# ESC.net
KiCad netlist of a schematic drawn in Altium Designer
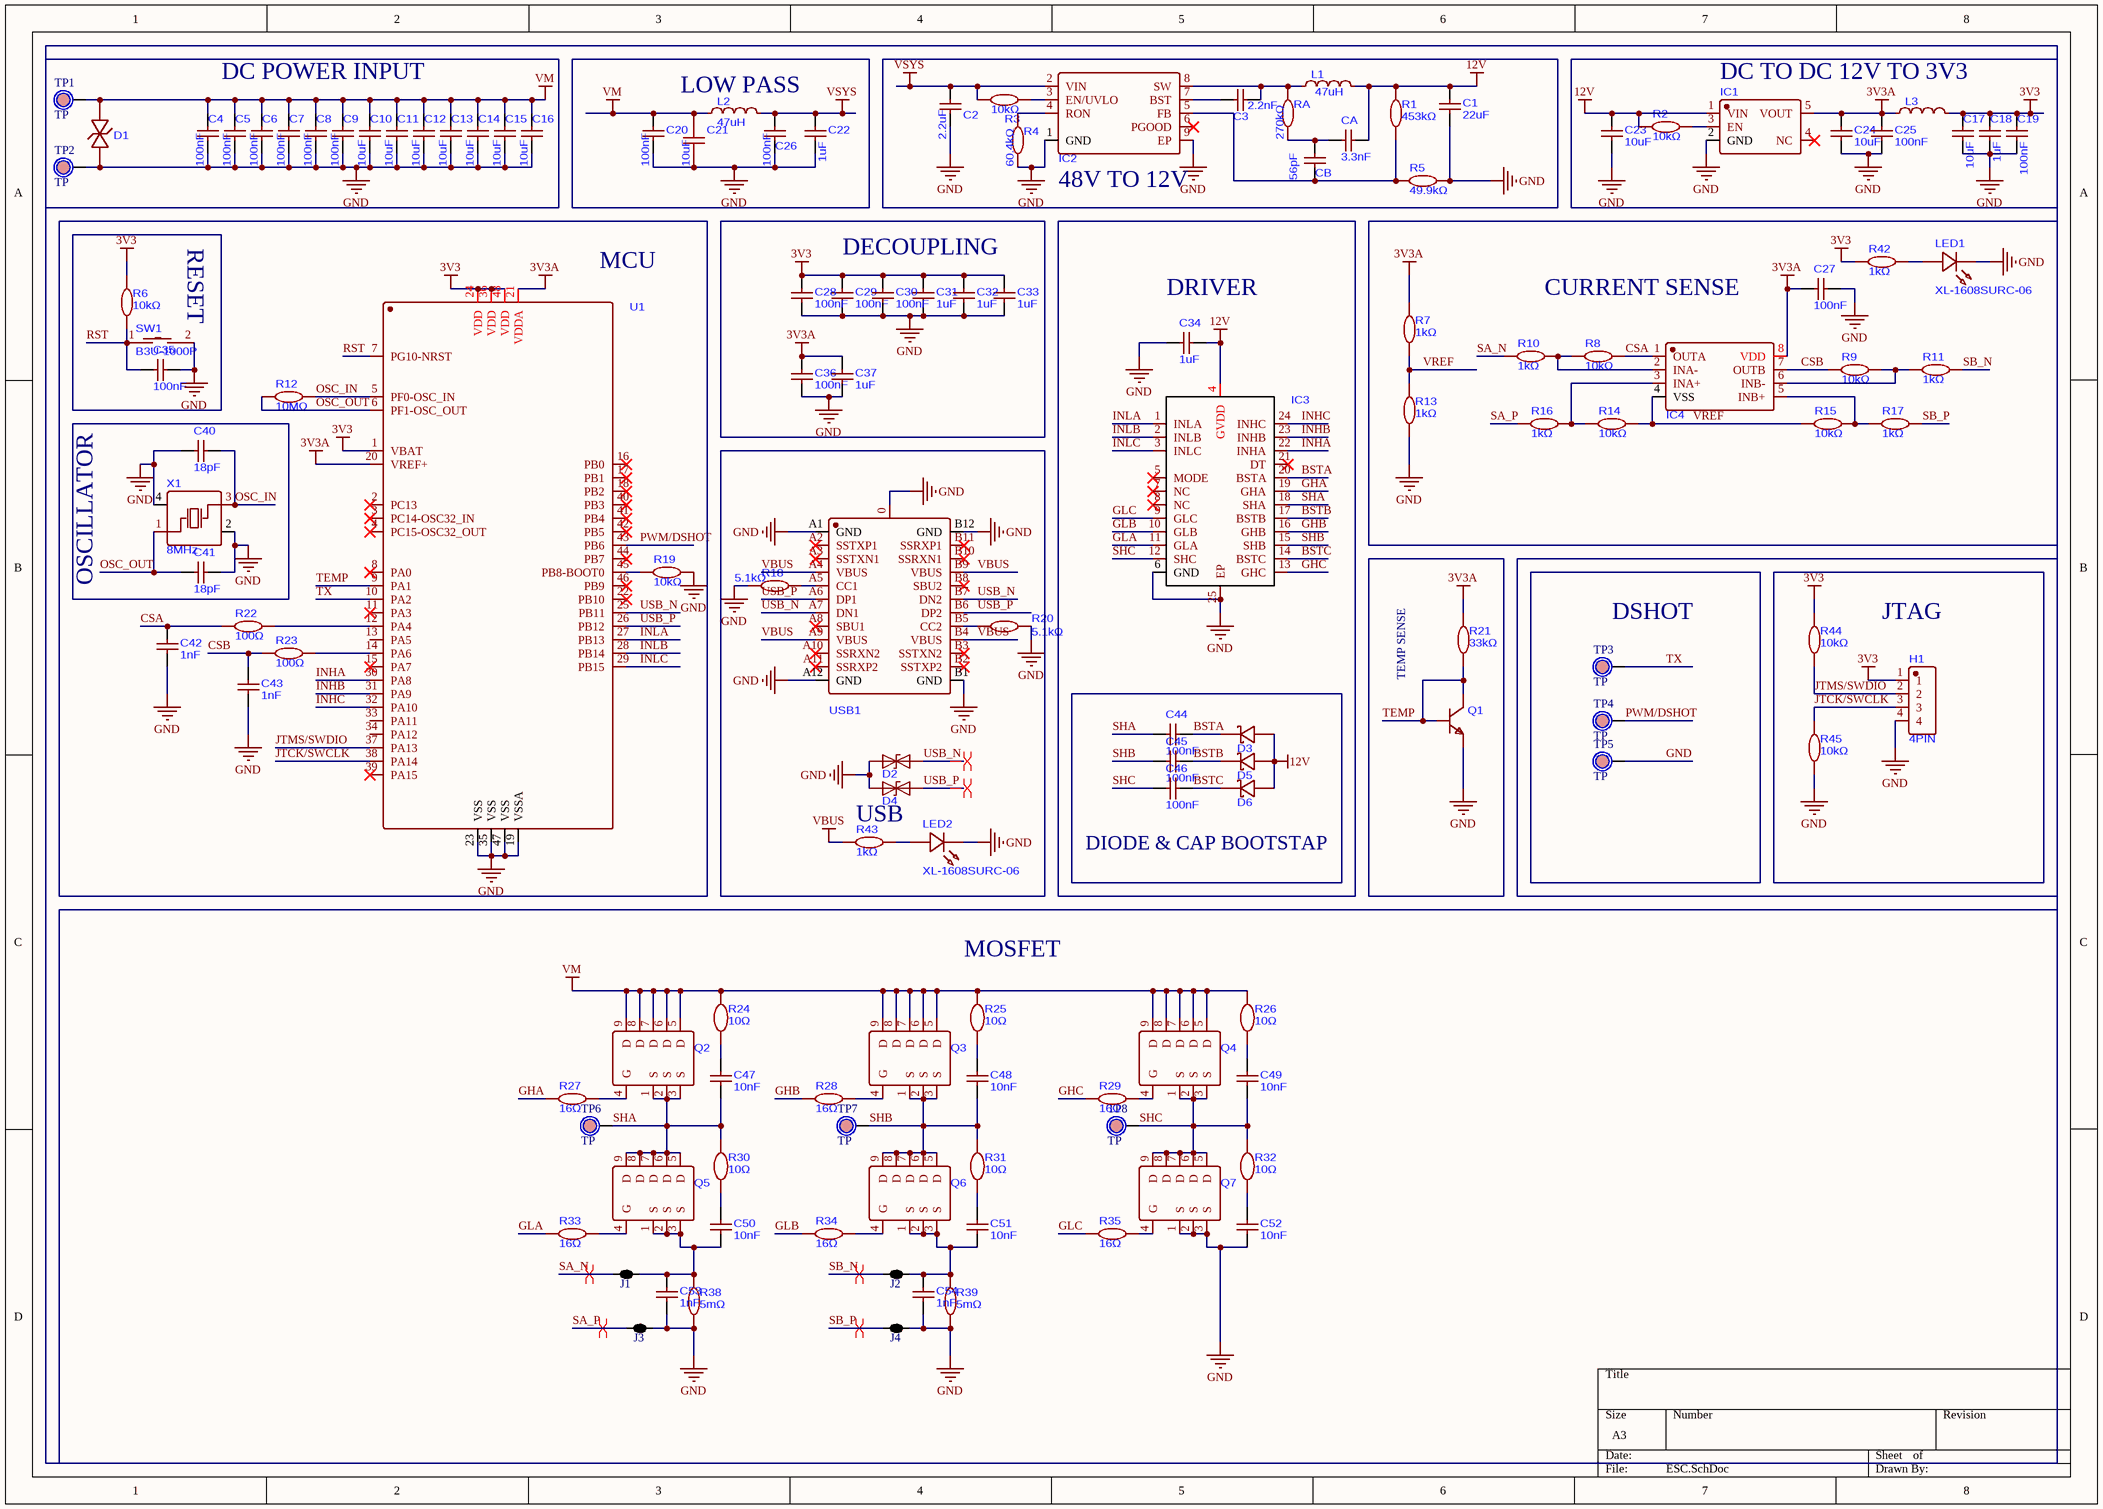
[diagram p0: ESC.SchDoc]

(export (version "E")
  (design (tool "Eeschema 10.0.6"))
  (components
    (comp (ref "C1")
      (value "22uF")
      (footprint "C0603")
      (description "CAP CER 22uF 25V 0603")
      (libsource (lib "ESC") (part "GRM188C61E226ME01D"))
    )
    (comp (ref "C2")
      (value "2.2uF")
      (footprint "C0805")
      (description "CAP CER 2.2uF 100V X7R 0805")
      (libsource (lib "ESC") (part "HHV0805R7225K101NSLJ"))
    )
    (comp (ref "C3")
      (value "2.2nF")
      (footprint "C0402")
      (description "CAP CER 2.2nF 50V X7R 0402")
      (libsource (lib "ESC") (part "GCM155R71H222KA37D"))
    )
    (comp (ref "C4")
      (value "100nF")
      (footprint "C0805")
      (description "100nF ±10% 100V Ceramic Capacitor X7R 0805")
      (libsource (lib "ESC") (part "CL21B104KCFNNNE"))
    )
    (comp (ref "C5")
      (value "100nF")
      (footprint "C0805")
      (description "100nF ±10% 100V Ceramic Capacitor X7R 0805")
      (libsource (lib "ESC") (part "CL21B104KCFNNNE"))
    )
    (comp (ref "C6")
      (value "100nF")
      (footprint "C0805")
      (description "100nF ±10% 100V Ceramic Capacitor X7R 0805")
      (libsource (lib "ESC") (part "CL21B104KCFNNNE"))
    )
    (comp (ref "C7")
      (value "100nF")
      (footprint "C0805")
      (description "100nF ±10% 100V Ceramic Capacitor X7R 0805")
      (libsource (lib "ESC") (part "CL21B104KCFNNNE"))
    )
    (comp (ref "C8")
      (value "100nF")
      (footprint "C0805")
      (description "100nF ±10% 100V Ceramic Capacitor X7R 0805")
      (libsource (lib "ESC") (part "CL21B104KCFNNNE"))
    )
    (comp (ref "C9")
      (value "100nF")
      (footprint "C0805")
      (description "100nF ±10% 100V Ceramic Capacitor X7R 0805")
      (libsource (lib "ESC") (part "CL21B104KCFNNNE"))
    )
    (comp (ref "C10")
      (value "10uF")
      (footprint "C1206")
      (description "10uF X6S ±10% 100V 1206 Ceramic Capacitors RoHS")
      (libsource (lib "ESC") (part "C3216X6S2A106KT0A0E"))
    )
    (comp (ref "C11")
      (value "10uF")
      (footprint "C1206")
      (description "10uF X6S ±10% 100V 1206 Ceramic Capacitors RoHS")
      (libsource (lib "ESC") (part "C3216X6S2A106KT0A0E"))
    )
    (comp (ref "C12")
      (value "10uF")
      (footprint "C1206")
      (description "10uF X6S ±10% 100V 1206 Ceramic Capacitors RoHS")
      (libsource (lib "ESC") (part "C3216X6S2A106KT0A0E"))
    )
    (comp (ref "C13")
      (value "10uF")
      (footprint "C1206")
      (description "10uF X6S ±10% 100V 1206 Ceramic Capacitors RoHS")
      (libsource (lib "ESC") (part "C3216X6S2A106KT0A0E"))
    )
    (comp (ref "C14")
      (value "10uF")
      (footprint "C1206")
      (description "10uF X6S ±10% 100V 1206 Ceramic Capacitors RoHS")
      (libsource (lib "ESC") (part "C3216X6S2A106KT0A0E"))
    )
    (comp (ref "C15")
      (value "10uF")
      (footprint "C1206")
      (description "10uF X6S ±10% 100V 1206 Ceramic Capacitors RoHS")
      (libsource (lib "ESC") (part "C3216X6S2A106KT0A0E"))
    )
    (comp (ref "C16")
      (value "10uF")
      (footprint "C1206")
      (description "10uF X6S ±10% 100V 1206 Ceramic Capacitors RoHS")
      (libsource (lib "ESC") (part "C3216X6S2A106KT0A0E"))
    )
    (comp (ref "C17")
      (value "10uF")
      (footprint "C0603")
      (description "CAP CER 10uF 25V X5R 0603")
      (libsource (lib "ESC") (part "CL10A106MA8NRNC"))
    )
    (comp (ref "C18")
      (value "1uF")
      (footprint "C0603")
      (description "1uF ±10% 100V Ceramic Capacitor X7T 0603")
      (libsource (lib "ESC") (part "GRM188D72A105KE01D"))
    )
    (comp (ref "C19")
      (value "100nF")
      (footprint "C0603")
      (description "100nF ±10% 50V Ceramic Capacitor X7R 0603")
      (libsource (lib "ESC") (part "CC0603KRX7R9BB104"))
    )
    (comp (ref "C20")
      (value "100nF")
      (footprint "C0805")
      (description "100nF ±10% 100V Ceramic Capacitor X7R 0805")
      (libsource (lib "ESC") (part "CL21B104KCFNNNE"))
    )
    (comp (ref "C21")
      (value "10uF")
      (footprint "C1206")
      (description "10uF X6S ±10% 100V 1206 Ceramic Capacitors RoHS")
      (libsource (lib "") (part "C3216X6S2A106KT0A0E_1"))
    )
    (comp (ref "C22")
      (value "1uF")
      (footprint "C0603")
      (description "1uF ±10% 100V Ceramic Capacitor X7T 0603")
      (libsource (lib "ESC") (part "GRM188D72A105KE01D"))
    )
    (comp (ref "C23")
      (value "10uF")
      (footprint "C0603")
      (description "CAP CER 10uF 25V X5R 0603")
      (libsource (lib "ESC") (part "CL10A106MA8NRNC"))
    )
    (comp (ref "C24")
      (value "10uF")
      (footprint "C0603")
      (description "CAP CER 10uF 25V X5R 0603")
      (libsource (lib "ESC") (part "CL10A106MA8NRNC"))
    )
    (comp (ref "C25")
      (value "100nF")
      (footprint "C0603")
      (description "100nF ±10% 50V Ceramic Capacitor X7R 0603")
      (libsource (lib "ESC") (part "CC0603KRX7R9BB104"))
    )
    (comp (ref "C26")
      (value "100nF")
      (footprint "C0805")
      (description "100nF ±10% 100V Ceramic Capacitor X7R 0805")
      (libsource (lib "ESC") (part "CL21B104KCFNNNE"))
    )
    (comp (ref "C27")
      (value "100nF")
      (footprint "C0402")
      (description "CAP CER 100nF 50V X7R 0402")
      (libsource (lib "ESC") (part "GRM155R71H104KE14D"))
    )
    (comp (ref "C28")
      (value "100nF")
      (footprint "C0402")
      (description "CAP CER 100nF 50V X7R 0402")
      (libsource (lib "ESC") (part "GRM155R71H104KE14D"))
    )
    (comp (ref "C29")
      (value "100nF")
      (footprint "C0402")
      (description "CAP CER 100nF 50V X7R 0402")
      (libsource (lib "ESC") (part "GRM155R71H104KE14D"))
    )
    (comp (ref "C30")
      (value "100nF")
      (footprint "C0402")
      (description "CAP CER 100nF 50V X7R 0402")
      (libsource (lib "ESC") (part "GRM155R71H104KE14D"))
    )
    (comp (ref "C31")
      (value "1uF")
      (footprint "C0402")
      (description "CAP CER 1uF 25V X5R 0402")
      (libsource (lib "ESC") (part "GRM155R61E105KA12D"))
    )
    (comp (ref "C32")
      (value "1uF")
      (footprint "C0402")
      (description "CAP CER 1uF 25V X5R 0402")
      (libsource (lib "ESC") (part "GRM155R61E105KA12D"))
    )
    (comp (ref "C33")
      (value "1uF")
      (footprint "C0402")
      (description "CAP CER 1uF 25V X5R 0402")
      (libsource (lib "ESC") (part "GRM155R61E105KA12D"))
    )
    (comp (ref "C34")
      (value "1uF")
      (footprint "C0402")
      (description "CAP CER 1uF 25V X5R 0402")
      (libsource (lib "ESC") (part "GRM155R61E105KA12D"))
    )
    (comp (ref "C35")
      (value "100nF")
      (footprint "C0402")
      (description "CAP CER 100nF 50V X7R 0402")
      (libsource (lib "ESC") (part "GRM155R71H104KE14D"))
    )
    (comp (ref "C36")
      (value "100nF")
      (footprint "C0402")
      (description "CAP CER 100nF 50V X7R 0402")
      (libsource (lib "ESC") (part "GRM155R71H104KE14D"))
    )
    (comp (ref "C37")
      (value "1uF")
      (footprint "C0402")
      (description "CAP CER 1uF 25V X5R 0402")
      (libsource (lib "ESC") (part "GRM155R61E105KA12D"))
    )
    (comp (ref "C40")
      (value "18pF")
      (footprint "C0402")
      (description "CAP CER 18pF 50V NP0 0402")
      (libsource (lib "ESC") (part "CC0402FRNPO9BN180"))
    )
    (comp (ref "C41")
      (value "18pF")
      (footprint "C0402")
      (description "CAP CER 18pF 50V NP0 0402")
      (libsource (lib "ESC") (part "CC0402FRNPO9BN180"))
    )
    (comp (ref "C42")
      (value "1nF")
      (footprint "C0402")
      (description "CAP CER 1nF 50V C0G 0402")
      (libsource (lib "ESC") (part "CL05C102JB5NNNC"))
    )
    (comp (ref "C43")
      (value "1nF")
      (footprint "C0402")
      (description "CAP CER 1nF 50V C0G 0402")
      (libsource (lib "ESC") (part "CL05C102JB5NNNC"))
    )
    (comp (ref "C44")
      (value "100nF")
      (footprint "C0402")
      (description "CAP CER 100nF 50V X7R 0402")
      (libsource (lib "ESC") (part "GRM155R71H104KE14D"))
    )
    (comp (ref "C45")
      (value "100nF")
      (footprint "C0402")
      (description "CAP CER 100nF 50V X7R 0402")
      (libsource (lib "ESC") (part "GRM155R71H104KE14D"))
    )
    (comp (ref "C46")
      (value "100nF")
      (footprint "C0402")
      (description "CAP CER 100nF 50V X7R 0402")
      (libsource (lib "ESC") (part "GRM155R71H104KE14D"))
    )
    (comp (ref "C47")
      (value "10nF")
      (footprint "C1206")
      (description "CAP CER 10nF 100V X7R 1206")
      (libsource (lib "ESC") (part "CC1206KRX7R0BB103"))
    )
    (comp (ref "C48")
      (value "10nF")
      (footprint "C1206")
      (description "CAP CER 10nF 100V X7R 1206")
      (libsource (lib "ESC") (part "CC1206KRX7R0BB103"))
    )
    (comp (ref "C49")
      (value "10nF")
      (footprint "C1206")
      (description "CAP CER 10nF 100V X7R 1206")
      (libsource (lib "ESC") (part "CC1206KRX7R0BB103"))
    )
    (comp (ref "C50")
      (value "10nF")
      (footprint "C1206")
      (description "CAP CER 10nF 100V X7R 1206")
      (libsource (lib "ESC") (part "CC1206KRX7R0BB103"))
    )
    (comp (ref "C51")
      (value "10nF")
      (footprint "C1206")
      (description "CAP CER 10nF 100V X7R 1206")
      (libsource (lib "ESC") (part "CC1206KRX7R0BB103"))
    )
    (comp (ref "C52")
      (value "10nF")
      (footprint "C1206")
      (description "CAP CER 10nF 100V X7R 1206")
      (libsource (lib "ESC") (part "CC1206KRX7R0BB103"))
    )
    (comp (ref "C53")
      (value "1nF")
      (footprint "C0402")
      (description "CAP CER 1nF 50V C0G 0402")
      (libsource (lib "ESC") (part "CL05C102JB5NNNC"))
    )
    (comp (ref "C54")
      (value "1nF")
      (footprint "C0402")
      (description "CAP CER 1nF 50V C0G 0402")
      (libsource (lib "ESC") (part "CL05C102JB5NNNC"))
    )
    (comp (ref "CA")
      (value "3.3nF")
      (footprint "C0603")
      (description "CAP CER 3.3nF 50V X7R 0603")
      (libsource (lib "ESC") (part "CL10B332KB8NNNC"))
    )
    (comp (ref "CB")
      (value "56pF")
      (footprint "C0603")
      (description "CAP CER 56pF 50V C0G 0603")
      (libsource (lib "ESC") (part "CL10C560JB8NNNC"))
    )
    (comp (ref "D1")
      (value "TVS DIODE 58VWM 85VC SMB")
      (footprint "DO-214AA_L4.4-W3.6-LS5.3-RD")
      (libsource (lib "ESC") (part "ESSMBJ58C2H"))
    )
    (comp (ref "D2")
      (value "TVS DIODE 5VWM 18.6VC SOD-523")
      (footprint "SOD-523_L1.2-W0.8-LS1.6-BI")
      (description "9.4A@8/20us 18.6V 7.8V 5V SOD-523 TVS Diodes RoHS")
      (libsource (lib "ESC") (part "LESD5D5.0CT1G"))
    )
    (comp (ref "D3")
      (value "DIODE SCHOTTKY 100V SOD-123FL")
      (footprint "SOD-123FL_L2.7-W1.8-LS3.8-RD")
      (libsource (lib "ESC") (part "DSS110"))
    )
    (comp (ref "D4")
      (value "TVS DIODE 5VWM 18.6VC SOD-523")
      (footprint "SOD-523_L1.2-W0.8-LS1.6-BI")
      (description "9.4A@8/20us 18.6V 7.8V 5V SOD-523 TVS Diodes RoHS")
      (libsource (lib "ESC") (part "LESD5D5.0CT1G"))
    )
    (comp (ref "D5")
      (value "DIODE SCHOTTKY 100V SOD-123FL")
      (footprint "SOD-123FL_L2.7-W1.8-LS3.8-RD")
      (libsource (lib "ESC") (part "DSS110"))
    )
    (comp (ref "D6")
      (value "DIODE SCHOTTKY 100V SOD-123FL")
      (footprint "SOD-123FL_L2.7-W1.8-LS3.8-RD")
      (libsource (lib "ESC") (part "DSS110"))
    )
    (comp (ref "H1")
      (value "4PIN")
      (footprint "HDR-TH_4P-P1.27-V-M")
      (description "CONN HEADER 4POS 1.27mm SINGLE ROW TH")
      (libsource (lib "ESC") (part "PZ127V-11-04-0720"))
    )
    (comp (ref "IC1")
      (value "500mA Low-Noise LDo Voltage Regulator")
      (footprint "SOT-23-5_L2.9-W1.6-P0.95-LS2.8-BR")
      (description "3.3V 16V Positive Fixed SOT-23-5 Voltage Regulators - Linear, Low Drop Out (LDO) Regulators RoHS")
      (libsource (lib "ESC") (part "SPX3819M5-L-3-3"))
    )
    (comp (ref "IC2")
      (value "100-V Input, 1-A Synchronous Buck DC/DC Converter")
      (footprint "SO-8_L4.9-W3.9-P1.27-LS6.0-BL-EP")
      (libsource (lib "ESC") (part "LM5164DDAR"))
    )
    (comp (ref "IC3")
      (value "100V three-phase BLDC gate driver")
      (footprint "QFN-24_L4.0-W4.0-P0.50-BL-EP2.7")
      (libsource (lib "ESC") (part "DRV8300NRGER"))
    )
    (comp (ref "IC4")
      (value "Zero-Drift CMOS Rail-to-Rail I/O Opamp with RF Filter")
      (footprint "MSOP-8_L3.0-W3.0-P0.65-LS5.0-BL")
      (libsource (lib "ESC") (part "GS8592-MR"))
    )
    (comp (ref "J1")
      (value "2 way net tie junction")
      (footprint "2way_LP")
      (libsource (lib "ESC") (part "2way"))
    )
    (comp (ref "J2")
      (value "2 way net tie junction")
      (footprint "2way_LP")
      (libsource (lib "ESC") (part "2way"))
    )
    (comp (ref "J3")
      (value "2 way net tie junction")
      (footprint "2way_LP")
      (libsource (lib "ESC") (part "2way"))
    )
    (comp (ref "J4")
      (value "2 way net tie junction")
      (footprint "2way_LP")
      (libsource (lib "ESC") (part "2way"))
    )
    (comp (ref "L1")
      (value "47uH")
      (footprint "IND-SMD_L6.0-W6.0")
      (description "FIXED IND 47uH 1.6A 200mΩ SMD,6x6mmSMD,5x5mm Fixed Inductors RoHS")
      (libsource (lib "ESC") (part "SRN6045TA-470M"))
    )
    (comp (ref "L2")
      (value "47uH")
      (footprint "IND-SMD_L5.0-W5.0_FNR50XXS")
      (description "1.15A 47uH ±20% 1.2A 354mΩ Magnetic Shielded Inductor SMD,5x5mm Fixed Inductors RoHS")
      (libsource (lib "ESC") (part "FNR5040S470MT"))
    )
    (comp (ref "L3")
      (value "FERRITE BEAD 120Ω 0603 1LN")
      (footprint "C0603")
      (libsource (lib "ESC") (part "BLM18PG121SN1D"))
    )
    (comp (ref "LED1")
      (value "XL-1608SURC-06")
      (footprint "LED0603-RD_RED")
      (description "20mA 2.3V Red 50mW 0603 LED Indication - Discrete ROHS")
      (libsource (lib "ESC") (part "XL-1608SURC-06"))
    )
    (comp (ref "LED2")
      (value "XL-1608SURC-06")
      (footprint "LED0603-RD_RED")
      (description "20mA 2.3V Red 50mW 0603 LED Indication - Discrete ROHS")
      (libsource (lib "ESC") (part "XL-1608SURC-06"))
    )
    (comp (ref "Q1")
      (value "TRANS NPN 40V 200mA SOT-416")
      (footprint "SC-75-3_L1.6-W0.8-P1.00-LS1.6-BR")
      (description "Bipolar (BJT) Transistor NPN 40V 200mA 300MHz 200mW Surface Mount SOT-416")
      (libsource (lib "ESC") (part "MMBT3904TT1G"))
    )
    (comp (ref "Q2")
      (value "MOSFET N-CH 85V 170A PDFN5x6-8L")
      (footprint "PDFN-8_L5.8-W5.1-P1.27-LS6.1-BL")
      (libsource (lib "ESC") (part "AGM028N08A"))
    )
    (comp (ref "Q3")
      (value "MOSFET N-CH 85V 170A PDFN5x6-8L")
      (footprint "PDFN-8_L5.8-W5.1-P1.27-LS6.1-BL")
      (libsource (lib "ESC") (part "AGM028N08A"))
    )
    (comp (ref "Q4")
      (value "MOSFET N-CH 85V 170A PDFN5x6-8L")
      (footprint "PDFN-8_L5.8-W5.1-P1.27-LS6.1-BL")
      (libsource (lib "ESC") (part "AGM028N08A"))
    )
    (comp (ref "Q5")
      (value "MOSFET N-CH 85V 170A PDFN5x6-8L")
      (footprint "PDFN-8_L5.8-W5.1-P1.27-LS6.1-BL")
      (libsource (lib "ESC") (part "AGM028N08A"))
    )
    (comp (ref "Q6")
      (value "MOSFET N-CH 85V 170A PDFN5x6-8L")
      (footprint "PDFN-8_L5.8-W5.1-P1.27-LS6.1-BL")
      (libsource (lib "ESC") (part "AGM028N08A"))
    )
    (comp (ref "Q7")
      (value "MOSFET N-CH 85V 170A PDFN5x6-8L")
      (footprint "PDFN-8_L5.8-W5.1-P1.27-LS6.1-BL")
      (libsource (lib "ESC") (part "AGM028N08A"))
    )
    (comp (ref "R1")
      (value "453kΩ")
      (footprint "R0603")
      (description "RES 453kΩ ±1% 100mW 0603")
      (libsource (lib "ESC") (part "FRC0603F4533TS"))
    )
    (comp (ref "R2")
      (value "10kΩ")
      (footprint "R0603")
      (description "100mW 10kΩ 75V ±100ppm/℃ Thick Film Resistor ±1% 0603 Chip Resistor - Surface Mount ROHS")
      (libsource (lib "ESC") (part "RC0603FR-0710KL"))
    )
    (comp (ref "R3")
      (value "10kΩ")
      (footprint "R0603")
      (description "100mW 10kΩ 75V ±100ppm/℃ Thick Film Resistor ±1% 0603 Chip Resistor - Surface Mount ROHS")
      (libsource (lib "ESC") (part "RC0603FR-0710KL"))
    )
    (comp (ref "R4")
      (value "60.4kΩ")
      (footprint "R0603")
      (description "RES 60.4kΩ ±1% 100mW 0603")
      (libsource (lib "ESC") (part "FRC0603F6042TS"))
    )
    (comp (ref "R5")
      (value "49.9kΩ")
      (footprint "R0603")
      (description "100mW 49.9kΩ 75V Thick Film Resistor ±100ppm/℃ ±1% 0603 Chip Resistor - Surface Mount RoHS")
      (libsource (lib "ESC") (part "RC0603FR-0749K9L"))
    )
    (comp (ref "R6")
      (value "10kΩ")
      (footprint "R0402")
      (description "RES 10kΩ ±0.1% 62.5mW 0402")
      (libsource (lib "ESC") (part "RT0402BRD0710KL"))
    )
    (comp (ref "R7")
      (value "1kΩ")
      (footprint "R0402")
      (description "RES 1kΩ ±0.1% 62.5mW 0402")
      (libsource (lib "ESC") (part "RT0402BRD071KL"))
    )
    (comp (ref "R8")
      (value "10kΩ")
      (footprint "R0402")
      (description "RES 10kΩ ±0.1% 62.5mW 0402")
      (libsource (lib "ESC") (part "RT0402BRD0710KL"))
    )
    (comp (ref "R9")
      (value "10kΩ")
      (footprint "R0402")
      (description "RES 10kΩ ±0.1% 62.5mW 0402")
      (libsource (lib "ESC") (part "RT0402BRD0710KL"))
    )
    (comp (ref "R10")
      (value "1kΩ")
      (footprint "R0402")
      (description "RES 1kΩ ±0.1% 62.5mW 0402")
      (libsource (lib "ESC") (part "RT0402BRD071KL"))
    )
    (comp (ref "R11")
      (value "1kΩ")
      (footprint "R0402")
      (description "RES 1kΩ ±0.1% 62.5mW 0402")
      (libsource (lib "ESC") (part "RT0402BRD071KL"))
    )
    (comp (ref "R12")
      (value "10MΩ")
      (footprint "R0402")
      (description "RES 1MΩ ±5% 62.5mW 0402")
      (libsource (lib "ESC") (part "FRC0402J105 TS"))
    )
    (comp (ref "R13")
      (value "1kΩ")
      (footprint "R0402")
      (description "RES 1kΩ ±0.1% 62.5mW 0402")
      (libsource (lib "ESC") (part "RT0402BRD071KL"))
    )
    (comp (ref "R14")
      (value "10kΩ")
      (footprint "R0402")
      (description "RES 10kΩ ±0.1% 62.5mW 0402")
      (libsource (lib "ESC") (part "RT0402BRD0710KL"))
    )
    (comp (ref "R15")
      (value "10kΩ")
      (footprint "R0402")
      (description "RES 10kΩ ±0.1% 62.5mW 0402")
      (libsource (lib "ESC") (part "RT0402BRD0710KL"))
    )
    (comp (ref "R16")
      (value "1kΩ")
      (footprint "R0402")
      (description "RES 1kΩ ±0.1% 62.5mW 0402")
      (libsource (lib "ESC") (part "RT0402BRD071KL"))
    )
    (comp (ref "R17")
      (value "1kΩ")
      (footprint "R0402")
      (description "RES 1kΩ ±0.1% 62.5mW 0402")
      (libsource (lib "ESC") (part "RT0402BRD071KL"))
    )
    (comp (ref "R18")
      (value "5.1kΩ")
      (footprint "R0402")
      (description "RES 5.1kΩ ±0.1% 62.5mW 0402")
      (libsource (lib "ESC") (part "RT0402BRD075K1L"))
    )
    (comp (ref "R19")
      (value "10kΩ")
      (footprint "R0402")
      (description "RES 10kΩ ±0.1% 62.5mW 0402")
      (libsource (lib "ESC") (part "RT0402BRD0710KL"))
    )
    (comp (ref "R20")
      (value "5.1kΩ")
      (footprint "R0402")
      (description "RES 5.1kΩ ±0.1% 62.5mW 0402")
      (libsource (lib "ESC") (part "RT0402BRD075K1L"))
    )
    (comp (ref "R21")
      (value "33kΩ")
      (footprint "R0402")
      (description "RES 33kΩ ±1% 62.5mW 0402")
      (libsource (lib "ESC") (part "FRC0402F3302TS"))
    )
    (comp (ref "R22")
      (value "100Ω")
      (footprint "R0402")
      (description "RES 100Ω ±0.1% 62.5mW 0402")
      (libsource (lib "ESC") (part "RT0402BRD07100RL"))
    )
    (comp (ref "R23")
      (value "100Ω")
      (footprint "R0402")
      (description "RES 100Ω ±0.1% 62.5mW 0402")
      (libsource (lib "ESC") (part "RT0402BRD07100RL"))
    )
    (comp (ref "R24")
      (value "10Ω")
      (footprint "R0612")
      (description "RES 10Ω ±1% 1W 0612")
      (libsource (lib "ESC") (part "WR121WF100JT5E"))
    )
    (comp (ref "R25")
      (value "10Ω")
      (footprint "R0612")
      (description "RES 10Ω ±1% 1W 0612")
      (libsource (lib "ESC") (part "WR121WF100JT5E"))
    )
    (comp (ref "R26")
      (value "10Ω")
      (footprint "R0612")
      (description "RES 10Ω ±1% 1W 0612")
      (libsource (lib "ESC") (part "WR121WF100JT5E"))
    )
    (comp (ref "R27")
      (value "16Ω")
      (footprint "R0402")
      (description "RES 16Ω ±5% 200mW 0402")
      (libsource (lib "ESC") (part "ERJPA2J160X"))
    )
    (comp (ref "R28")
      (value "16Ω")
      (footprint "R0402")
      (description "RES 16Ω ±5% 200mW 0402")
      (libsource (lib "ESC") (part "ERJPA2J160X"))
    )
    (comp (ref "R29")
      (value "16Ω")
      (footprint "R0402")
      (description "RES 16Ω ±5% 200mW 0402")
      (libsource (lib "ESC") (part "ERJPA2J160X"))
    )
    (comp (ref "R30")
      (value "10Ω")
      (footprint "R0612")
      (description "RES 10Ω ±1% 1W 0612")
      (libsource (lib "ESC") (part "WR121WF100JT5E"))
    )
    (comp (ref "R31")
      (value "10Ω")
      (footprint "R0612")
      (description "RES 10Ω ±1% 1W 0612")
      (libsource (lib "ESC") (part "WR121WF100JT5E"))
    )
    (comp (ref "R32")
      (value "10Ω")
      (footprint "R0612")
      (description "RES 10Ω ±1% 1W 0612")
      (libsource (lib "ESC") (part "WR121WF100JT5E"))
    )
    (comp (ref "R33")
      (value "16Ω")
      (footprint "R0402")
      (description "RES 16Ω ±5% 200mW 0402")
      (libsource (lib "ESC") (part "ERJPA2J160X"))
    )
    (comp (ref "R34")
      (value "16Ω")
      (footprint "R0402")
      (description "RES 16Ω ±5% 200mW 0402")
      (libsource (lib "ESC") (part "ERJPA2J160X"))
    )
    (comp (ref "R35")
      (value "16Ω")
      (footprint "R0402")
      (description "RES 16Ω ±5% 200mW 0402")
      (libsource (lib "ESC") (part "ERJPA2J160X"))
    )
    (comp (ref "R38")
      (value "5mΩ")
      (footprint "R2512")
      (description "RES 5mΩ ±1% 3W 2512")
      (libsource (lib "ESC") (part "RLP25FEGMR005"))
    )
    (comp (ref "R39")
      (value "5mΩ")
      (footprint "R2512")
      (description "RES 5mΩ ±1% 3W 2512")
      (libsource (lib "ESC") (part "RLP25FEGMR005"))
    )
    (comp (ref "R42")
      (value "1kΩ")
      (footprint "R0402")
      (description "RES 1kΩ ±0.1% 62.5mW 0402")
      (libsource (lib "ESC") (part "RT0402BRD071KL"))
    )
    (comp (ref "R43")
      (value "1kΩ")
      (footprint "R0402")
      (description "RES 1kΩ ±0.1% 62.5mW 0402")
      (libsource (lib "ESC") (part "RT0402BRD071KL"))
    )
    (comp (ref "R44")
      (value "10kΩ")
      (footprint "R0402")
      (description "RES 10kΩ ±0.1% 62.5mW 0402")
      (libsource (lib "ESC") (part "RT0402BRD0710KL"))
    )
    (comp (ref "R45")
      (value "10kΩ")
      (footprint "R0402")
      (description "RES 10kΩ ±0.1% 62.5mW 0402")
      (libsource (lib "ESC") (part "RT0402BRD0710KL"))
    )
    (comp (ref "RA")
      (value "270kΩ")
      (footprint "R0603")
      (description "RES 270kΩ ±0.1% 100mW 0603")
      (libsource (lib "ESC") (part "AR03BTCX2703"))
    )
    (comp (ref "SW1")
      (value "B3U-1000P")
      (footprint "KEY-SMD_B3U-1000PM")
      (description "12V 2.5mm Round Button 3mm SPST 50mA SMD,3x2.5mm Tactile Switches ROHS")
      (libsource (lib "ESC") (part "B3U-1000P"))
    )
    (comp (ref "TP1")
      (value "TP")
      (footprint "PAD")
      (description "Test Point")
      (libsource (lib "ESC") (part "Test_point_DNM"))
    )
    (comp (ref "TP2")
      (value "TP")
      (footprint "PAD")
      (description "Test Point")
      (libsource (lib "ESC") (part "Test_point_DNM"))
    )
    (comp (ref "TP3")
      (value "TP")
      (footprint "PAD")
      (description "Test Point")
      (libsource (lib "ESC") (part "Test_point_DNM"))
    )
    (comp (ref "TP4")
      (value "TP")
      (footprint "PAD")
      (description "Test Point")
      (libsource (lib "ESC") (part "Test_point_DNM"))
    )
    (comp (ref "TP5")
      (value "TP")
      (footprint "PAD")
      (description "Test Point")
      (libsource (lib "ESC") (part "Test_point_DNM"))
    )
    (comp (ref "TP6")
      (value "TP")
      (footprint "PAD")
      (description "Test Point")
      (libsource (lib "ESC") (part "Test_point_DNM"))
    )
    (comp (ref "TP7")
      (value "TP")
      (footprint "PAD")
      (description "Test Point")
      (libsource (lib "ESC") (part "Test_point_DNM"))
    )
    (comp (ref "TP8")
      (value "TP")
      (footprint "PAD")
      (description "Test Point")
      (libsource (lib "ESC") (part "Test_point_DNM"))
    )
    (comp (ref "U1")
      (value "Arm Cortex-M4 32-bit MCU+FPU, 170 MHz / 213 DMIPS, up to 128 KB Flash, 32 KB SRAM, rich analog, math accelerator")
      (footprint "LQFP-48_L7.0-W7.0-P0.50-LS9.0-BL")
      (libsource (lib "ESC") (part "STM32G431CBT6"))
    )
    (comp (ref "USB1")
      (value "CONN RCPT Type-C 24POS SMD")
      (footprint "USB-C-SMD_U263-241N-4BQC14")
      (libsource (lib "ESC") (part "U263-241N-4BQC14"))
    )
    (comp (ref "X1")
      (value "8MHz")
      (footprint "OSC-SMD_4P-L5.0-W3.2-BL")
      (description "Crystal 8MHz ±10ppm 10pF 200Ω SMD5032-4P")
      (libsource (lib "ESC") (part "ABM3B-8.000MHZ-10-1-U-T"))
    )
  )
  (nets
    (net (code "1") (name "/BSTA") (class "Default")
      (node (ref "C44") (pin "2") (pinfunction "2_2") (pintype "passive"))
      (node (ref "D3") (pin "1") (pinfunction "1_1") (pintype "passive"))
      (node (ref "IC3") (pin "20") (pinfunction "BSTA_20") (pintype "passive"))
    )
    (net (code "2") (name "/BSTB") (class "Default")
      (node (ref "C45") (pin "2") (pinfunction "2_2") (pintype "passive"))
      (node (ref "D5") (pin "1") (pinfunction "1_1") (pintype "passive"))
      (node (ref "IC3") (pin "17") (pinfunction "BSTB_17") (pintype "passive"))
    )
    (net (code "3") (name "/BSTC") (class "Default")
      (node (ref "C46") (pin "2") (pinfunction "2_2") (pintype "passive"))
      (node (ref "D6") (pin "1") (pinfunction "1_1") (pintype "passive"))
      (node (ref "IC3") (pin "14") (pinfunction "BSTC_14") (pintype "passive"))
    )
    (net (code "4") (name "/CSA") (class "Default")
      (node (ref "C42") (pin "2") (pinfunction "2_2") (pintype "passive"))
      (node (ref "IC4") (pin "1") (pinfunction "OUTA_1") (pintype "passive"))
      (node (ref "R22") (pin "1") (pinfunction "1_1") (pintype "passive"))
      (node (ref "R8") (pin "2") (pinfunction "2_2") (pintype "passive"))
    )
    (net (code "5") (name "/CSB") (class "Default")
      (node (ref "C43") (pin "2") (pinfunction "2_2") (pintype "passive"))
      (node (ref "IC4") (pin "7") (pinfunction "OUTB_7") (pintype "passive"))
      (node (ref "R23") (pin "1") (pinfunction "1_1") (pintype "passive"))
      (node (ref "R9") (pin "1") (pinfunction "1_1") (pintype "passive"))
    )
    (net (code "6") (name "/GHA") (class "Default")
      (node (ref "IC3") (pin "19") (pinfunction "GHA_19") (pintype "passive"))
      (node (ref "R27") (pin "1") (pinfunction "1_1") (pintype "passive"))
    )
    (net (code "7") (name "/GHB") (class "Default")
      (node (ref "IC3") (pin "16") (pinfunction "GHB_16") (pintype "passive"))
      (node (ref "R28") (pin "1") (pinfunction "1_1") (pintype "passive"))
    )
    (net (code "8") (name "/GHC") (class "Default")
      (node (ref "IC3") (pin "13") (pinfunction "GHC_13") (pintype "passive"))
      (node (ref "R29") (pin "1") (pinfunction "1_1") (pintype "passive"))
    )
    (net (code "9") (name "/GLA") (class "Default")
      (node (ref "IC3") (pin "11") (pinfunction "GLA_11") (pintype "passive"))
      (node (ref "R33") (pin "1") (pinfunction "1_1") (pintype "passive"))
    )
    (net (code "10") (name "/GLB") (class "Default")
      (node (ref "IC3") (pin "10") (pinfunction "GLB_10") (pintype "passive"))
      (node (ref "R34") (pin "1") (pinfunction "1_1") (pintype "passive"))
    )
    (net (code "11") (name "/GLC") (class "Default")
      (node (ref "IC3") (pin "9") (pinfunction "GLC_9") (pintype "passive"))
      (node (ref "R35") (pin "1") (pinfunction "1_1") (pintype "passive"))
    )
    (net (code "12") (name "/INHA") (class "Default")
      (node (ref "IC3") (pin "22") (pinfunction "INHA_22") (pintype "passive"))
      (node (ref "U1") (pin "30") (pinfunction "PA8_30") (pintype "passive"))
    )
    (net (code "13") (name "/INHB") (class "Default")
      (node (ref "IC3") (pin "23") (pinfunction "INHB_23") (pintype "passive"))
      (node (ref "U1") (pin "31") (pinfunction "PA9_31") (pintype "passive"))
    )
    (net (code "14") (name "/INHC") (class "Default")
      (node (ref "IC3") (pin "24") (pinfunction "INHC_24") (pintype "passive"))
      (node (ref "U1") (pin "32") (pinfunction "PA10_32") (pintype "passive"))
    )
    (net (code "15") (name "/INLA") (class "Default")
      (node (ref "IC3") (pin "1") (pinfunction "INLA_1") (pintype "passive"))
      (node (ref "U1") (pin "27") (pinfunction "PB13_27") (pintype "passive"))
    )
    (net (code "16") (name "/INLB") (class "Default")
      (node (ref "IC3") (pin "2") (pinfunction "INLB_2") (pintype "passive"))
      (node (ref "U1") (pin "28") (pinfunction "PB14_28") (pintype "passive"))
    )
    (net (code "17") (name "/INLC") (class "Default")
      (node (ref "IC3") (pin "3") (pinfunction "INLC_3") (pintype "passive"))
      (node (ref "U1") (pin "29") (pinfunction "PB15_29") (pintype "passive"))
    )
    (net (code "18") (name "/JTCK{slash}SWCLK") (class "Default")
      (node (ref "H1") (pin "3") (pinfunction "3_3") (pintype "passive"))
      (node (ref "R45") (pin "2") (pinfunction "2_2") (pintype "passive"))
      (node (ref "U1") (pin "38") (pinfunction "PA14_38") (pintype "passive"))
    )
    (net (code "19") (name "/JTMS{slash}SWDIO") (class "Default")
      (node (ref "H1") (pin "2") (pinfunction "2_2") (pintype "passive"))
      (node (ref "R44") (pin "1") (pinfunction "1_1") (pintype "passive"))
      (node (ref "U1") (pin "37") (pinfunction "PA13_37") (pintype "passive"))
    )
    (net (code "20") (name "/OSC_IN") (class "Default")
      (node (ref "C40") (pin "2") (pinfunction "2_2") (pintype "passive"))
      (node (ref "R12") (pin "2") (pinfunction "2_2") (pintype "passive"))
      (node (ref "U1") (pin "5") (pinfunction "PF0-OSC_IN_5") (pintype "passive"))
      (node (ref "X1") (pin "3") (pinfunction "OSC2_3") (pintype "passive"))
    )
    (net (code "21") (name "/OSC_OUT") (class "Default")
      (node (ref "C41") (pin "1") (pinfunction "1_1") (pintype "passive"))
      (node (ref "R12") (pin "1") (pinfunction "1_1") (pintype "passive"))
      (node (ref "U1") (pin "6") (pinfunction "PF1-OSC_OUT_6") (pintype "passive"))
      (node (ref "X1") (pin "1") (pinfunction "OSC1_1") (pintype "passive"))
    )
    (net (code "22") (name "/PWM{slash}DSHOT") (class "Default")
      (node (ref "TP4") (pin "1") (pinfunction "1_1") (pintype "passive"))
      (node (ref "U1") (pin "43") (pinfunction "PB6_43") (pintype "passive"))
    )
    (net (code "23") (name "/RST") (class "Default")
      (node (ref "C35") (pin "1") (pinfunction "1_1") (pintype "passive"))
      (node (ref "R6") (pin "1") (pinfunction "1_1") (pintype "passive"))
      (node (ref "SW1") (pin "1") (pinfunction "1_1") (pintype "passive"))
      (node (ref "U1") (pin "7") (pinfunction "PG10-NRST_7") (pintype "passive"))
    )
    (net (code "24") (name "/SA_N") (class "Default")
      (node (ref "J1") (pin "1") (pinfunction "1_1") (pintype "passive"))
      (node (ref "R10") (pin "1") (pinfunction "1_1") (pintype "passive"))
    )
    (net (code "25") (name "/SA_P") (class "Default")
      (node (ref "J3") (pin "1") (pinfunction "1_1") (pintype "passive"))
      (node (ref "R16") (pin "1") (pinfunction "1_1") (pintype "passive"))
    )
    (net (code "26") (name "/SB_N") (class "Default")
      (node (ref "J2") (pin "1") (pinfunction "1_1") (pintype "passive"))
      (node (ref "R11") (pin "2") (pinfunction "2_2") (pintype "passive"))
    )
    (net (code "27") (name "/SB_P") (class "Default")
      (node (ref "J4") (pin "1") (pinfunction "1_1") (pintype "passive"))
      (node (ref "R17") (pin "2") (pinfunction "2_2") (pintype "passive"))
    )
    (net (code "28") (name "/SHA") (class "Default")
      (node (ref "C44") (pin "1") (pinfunction "1_1") (pintype "passive"))
      (node (ref "C47") (pin "1") (pinfunction "1_1") (pintype "passive"))
      (node (ref "IC3") (pin "18") (pinfunction "SHA_18") (pintype "passive"))
      (node (ref "Q2") (pin "1") (pinfunction "S_1") (pintype "passive"))
      (node (ref "Q2") (pin "2") (pinfunction "S_2") (pintype "passive"))
      (node (ref "Q2") (pin "3") (pinfunction "S_3") (pintype "passive"))
      (node (ref "Q5") (pin "5") (pinfunction "D_5") (pintype "passive"))
      (node (ref "Q5") (pin "6") (pinfunction "D_6") (pintype "passive"))
      (node (ref "Q5") (pin "7") (pinfunction "D_7") (pintype "passive"))
      (node (ref "Q5") (pin "8") (pinfunction "D_8") (pintype "passive"))
      (node (ref "Q5") (pin "9") (pinfunction "D_9") (pintype "passive"))
      (node (ref "R30") (pin "2") (pinfunction "2_2") (pintype "passive"))
      (node (ref "TP6") (pin "1") (pinfunction "1_1") (pintype "passive"))
    )
    (net (code "29") (name "/SHB") (class "Default")
      (node (ref "C45") (pin "1") (pinfunction "1_1") (pintype "passive"))
      (node (ref "C48") (pin "1") (pinfunction "1_1") (pintype "passive"))
      (node (ref "IC3") (pin "15") (pinfunction "SHB_15") (pintype "passive"))
      (node (ref "Q3") (pin "1") (pinfunction "S_1") (pintype "passive"))
      (node (ref "Q3") (pin "2") (pinfunction "S_2") (pintype "passive"))
      (node (ref "Q3") (pin "3") (pinfunction "S_3") (pintype "passive"))
      (node (ref "Q6") (pin "5") (pinfunction "D_5") (pintype "passive"))
      (node (ref "Q6") (pin "6") (pinfunction "D_6") (pintype "passive"))
      (node (ref "Q6") (pin "7") (pinfunction "D_7") (pintype "passive"))
      (node (ref "Q6") (pin "8") (pinfunction "D_8") (pintype "passive"))
      (node (ref "Q6") (pin "9") (pinfunction "D_9") (pintype "passive"))
      (node (ref "R31") (pin "2") (pinfunction "2_2") (pintype "passive"))
      (node (ref "TP7") (pin "1") (pinfunction "1_1") (pintype "passive"))
    )
    (net (code "30") (name "/SHC") (class "Default")
      (node (ref "C46") (pin "1") (pinfunction "1_1") (pintype "passive"))
      (node (ref "C49") (pin "1") (pinfunction "1_1") (pintype "passive"))
      (node (ref "IC3") (pin "12") (pinfunction "SHC_12") (pintype "passive"))
      (node (ref "Q4") (pin "1") (pinfunction "S_1") (pintype "passive"))
      (node (ref "Q4") (pin "2") (pinfunction "S_2") (pintype "passive"))
      (node (ref "Q4") (pin "3") (pinfunction "S_3") (pintype "passive"))
      (node (ref "Q7") (pin "5") (pinfunction "D_5") (pintype "passive"))
      (node (ref "Q7") (pin "6") (pinfunction "D_6") (pintype "passive"))
      (node (ref "Q7") (pin "7") (pinfunction "D_7") (pintype "passive"))
      (node (ref "Q7") (pin "8") (pinfunction "D_8") (pintype "passive"))
      (node (ref "Q7") (pin "9") (pinfunction "D_9") (pintype "passive"))
      (node (ref "R32") (pin "2") (pinfunction "2_2") (pintype "passive"))
      (node (ref "TP8") (pin "1") (pinfunction "1_1") (pintype "passive"))
    )
    (net (code "31") (name "/TEMP") (class "Default")
      (node (ref "Q1") (pin "1") (pinfunction "B_1") (pintype "passive"))
      (node (ref "Q1") (pin "3") (pinfunction "C_3") (pintype "passive"))
      (node (ref "R21") (pin "1") (pinfunction "1_1") (pintype "passive"))
      (node (ref "U1") (pin "9") (pinfunction "PA1_9") (pintype "passive"))
    )
    (net (code "32") (name "/TX") (class "Default")
      (node (ref "TP3") (pin "1") (pinfunction "1_1") (pintype "passive"))
      (node (ref "U1") (pin "10") (pinfunction "PA2_10") (pintype "passive"))
    )
    (net (code "33") (name "/USB_N") (class "Default")
      (node (ref "D2") (pin "2") (pinfunction "A_2") (pintype "passive"))
      (node (ref "U1") (pin "25") (pinfunction "PB11_25") (pintype "passive"))
      (node (ref "USB1") (pin "A7") (pinfunction "DN1_A7") (pintype "passive"))
      (node (ref "USB1") (pin "B7") (pinfunction "DN2_B7") (pintype "passive"))
    )
    (net (code "34") (name "/USB_P") (class "Default")
      (node (ref "D4") (pin "2") (pinfunction "A_2") (pintype "passive"))
      (node (ref "U1") (pin "26") (pinfunction "PB12_26") (pintype "passive"))
      (node (ref "USB1") (pin "A6") (pinfunction "DP1_A6") (pintype "passive"))
      (node (ref "USB1") (pin "B6") (pinfunction "DP2_B6") (pintype "passive"))
    )
    (net (code "35") (name "/VREF") (class "Default")
      (node (ref "IC4") (pin "4") (pinfunction "VSS_4") (pintype "passive"))
      (node (ref "R13") (pin "2") (pinfunction "2_2") (pintype "passive"))
      (node (ref "R14") (pin "2") (pinfunction "2_2") (pintype "passive"))
      (node (ref "R15") (pin "1") (pinfunction "1_1") (pintype "passive"))
      (node (ref "R7") (pin "1") (pinfunction "1_1") (pintype "passive"))
    )
    (net (code "36") (name "3V3") (class "Default")
      (node (ref "C17") (pin "2") (pinfunction "2_2") (pintype "passive"))
      (node (ref "C18") (pin "2") (pinfunction "2_2") (pintype "passive"))
      (node (ref "C19") (pin "2") (pinfunction "2_2") (pintype "passive"))
      (node (ref "C28") (pin "2") (pinfunction "2_2") (pintype "passive"))
      (node (ref "C29") (pin "2") (pinfunction "2_2") (pintype "passive"))
      (node (ref "C30") (pin "2") (pinfunction "2_2") (pintype "passive"))
      (node (ref "C31") (pin "2") (pinfunction "2_2") (pintype "passive"))
      (node (ref "C32") (pin "2") (pinfunction "2_2") (pintype "passive"))
      (node (ref "C33") (pin "2") (pinfunction "2_2") (pintype "passive"))
      (node (ref "H1") (pin "1") (pinfunction "1_1") (pintype "passive"))
      (node (ref "L3") (pin "2") (pinfunction "2_2") (pintype "passive"))
      (node (ref "R42") (pin "1") (pinfunction "1_1") (pintype "passive"))
      (node (ref "R44") (pin "2") (pinfunction "2_2") (pintype "passive"))
      (node (ref "R6") (pin "2") (pinfunction "2_2") (pintype "passive"))
      (node (ref "U1") (pin "1") (pinfunction "VBAT_1") (pintype "passive"))
      (node (ref "U1") (pin "24") (pinfunction "VDD_24") (pintype "passive"))
      (node (ref "U1") (pin "36") (pinfunction "VDD_36") (pintype "passive"))
      (node (ref "U1") (pin "48") (pinfunction "VDD_48") (pintype "passive"))
    )
    (net (code "37") (name "3V3A") (class "Default")
      (node (ref "C24") (pin "2") (pinfunction "2_2") (pintype "passive"))
      (node (ref "C25") (pin "2") (pinfunction "2_2") (pintype "passive"))
      (node (ref "C27") (pin "2") (pinfunction "2_2") (pintype "passive"))
      (node (ref "C36") (pin "2") (pinfunction "2_2") (pintype "passive"))
      (node (ref "C37") (pin "2") (pinfunction "2_2") (pintype "passive"))
      (node (ref "IC1") (pin "5") (pinfunction "VOUT_5") (pintype "passive"))
      (node (ref "IC4") (pin "8") (pinfunction "VDD_8") (pintype "passive"))
      (node (ref "L3") (pin "1") (pinfunction "1_1") (pintype "passive"))
      (node (ref "R21") (pin "2") (pinfunction "2_2") (pintype "passive"))
      (node (ref "R7") (pin "2") (pinfunction "2_2") (pintype "passive"))
      (node (ref "U1") (pin "20") (pinfunction "VREF+_20") (pintype "passive"))
      (node (ref "U1") (pin "21") (pinfunction "VDDA_21") (pintype "passive"))
    )
    (net (code "38") (name "12V") (class "Default")
      (node (ref "C1") (pin "2") (pinfunction "2_2") (pintype "passive"))
      (node (ref "C23") (pin "2") (pinfunction "2_2") (pintype "passive"))
      (node (ref "C34") (pin "2") (pinfunction "2_2") (pintype "passive"))
      (node (ref "CA") (pin "2") (pinfunction "2_2") (pintype "passive"))
      (node (ref "D3") (pin "2") (pinfunction "2_2") (pintype "passive"))
      (node (ref "D5") (pin "2") (pinfunction "2_2") (pintype "passive"))
      (node (ref "D6") (pin "2") (pinfunction "2_2") (pintype "passive"))
      (node (ref "IC1") (pin "1") (pinfunction "VIN_1") (pintype "passive"))
      (node (ref "IC3") (pin "4") (pinfunction "GVDD_4") (pintype "passive"))
      (node (ref "L1") (pin "2") (pinfunction "2_2") (pintype "passive"))
      (node (ref "R1") (pin "2") (pinfunction "2_2") (pintype "passive"))
      (node (ref "R2") (pin "1") (pinfunction "1_1") (pintype "passive"))
    )
    (net (code "39") (name "GND") (class "Default")
      (node (ref "C1") (pin "1") (pinfunction "1_1") (pintype "passive"))
      (node (ref "C10") (pin "1") (pinfunction "1_1") (pintype "passive"))
      (node (ref "C11") (pin "1") (pinfunction "1_1") (pintype "passive"))
      (node (ref "C12") (pin "1") (pinfunction "1_1") (pintype "passive"))
      (node (ref "C13") (pin "1") (pinfunction "1_1") (pintype "passive"))
      (node (ref "C14") (pin "1") (pinfunction "1_1") (pintype "passive"))
      (node (ref "C15") (pin "1") (pinfunction "1_1") (pintype "passive"))
      (node (ref "C16") (pin "1") (pinfunction "1_1") (pintype "passive"))
      (node (ref "C17") (pin "1") (pinfunction "1_1") (pintype "passive"))
      (node (ref "C18") (pin "1") (pinfunction "1_1") (pintype "passive"))
      (node (ref "C19") (pin "1") (pinfunction "1_1") (pintype "passive"))
      (node (ref "C2") (pin "1") (pinfunction "1_1") (pintype "passive"))
      (node (ref "C20") (pin "1") (pinfunction "1_1") (pintype "passive"))
      (node (ref "C21") (pin "1") (pinfunction "1_1") (pintype "passive"))
      (node (ref "C22") (pin "1") (pinfunction "1_1") (pintype "passive"))
      (node (ref "C23") (pin "1") (pinfunction "1_1") (pintype "passive"))
      (node (ref "C24") (pin "1") (pinfunction "1_1") (pintype "passive"))
      (node (ref "C25") (pin "1") (pinfunction "1_1") (pintype "passive"))
      (node (ref "C26") (pin "1") (pinfunction "1_1") (pintype "passive"))
      (node (ref "C27") (pin "1") (pinfunction "1_1") (pintype "passive"))
      (node (ref "C28") (pin "1") (pinfunction "1_1") (pintype "passive"))
      (node (ref "C29") (pin "1") (pinfunction "1_1") (pintype "passive"))
      (node (ref "C30") (pin "1") (pinfunction "1_1") (pintype "passive"))
      (node (ref "C31") (pin "1") (pinfunction "1_1") (pintype "passive"))
      (node (ref "C32") (pin "1") (pinfunction "1_1") (pintype "passive"))
      (node (ref "C33") (pin "1") (pinfunction "1_1") (pintype "passive"))
      (node (ref "C34") (pin "1") (pinfunction "1_1") (pintype "passive"))
      (node (ref "C35") (pin "2") (pinfunction "2_2") (pintype "passive"))
      (node (ref "C36") (pin "1") (pinfunction "1_1") (pintype "passive"))
      (node (ref "C37") (pin "1") (pinfunction "1_1") (pintype "passive"))
      (node (ref "C4") (pin "1") (pinfunction "1_1") (pintype "passive"))
      (node (ref "C40") (pin "1") (pinfunction "1_1") (pintype "passive"))
      (node (ref "C41") (pin "2") (pinfunction "2_2") (pintype "passive"))
      (node (ref "C42") (pin "1") (pinfunction "1_1") (pintype "passive"))
      (node (ref "C43") (pin "1") (pinfunction "1_1") (pintype "passive"))
      (node (ref "C5") (pin "1") (pinfunction "1_1") (pintype "passive"))
      (node (ref "C52") (pin "1") (pinfunction "1_1") (pintype "passive"))
      (node (ref "C53") (pin "1") (pinfunction "1_1") (pintype "passive"))
      (node (ref "C54") (pin "1") (pinfunction "1_1") (pintype "passive"))
      (node (ref "C6") (pin "1") (pinfunction "1_1") (pintype "passive"))
      (node (ref "C7") (pin "1") (pinfunction "1_1") (pintype "passive"))
      (node (ref "C8") (pin "1") (pinfunction "1_1") (pintype "passive"))
      (node (ref "C9") (pin "1") (pinfunction "1_1") (pintype "passive"))
      (node (ref "D1") (pin "1") (pinfunction "1_1") (pintype "passive"))
      (node (ref "D2") (pin "1") (pinfunction "K_1") (pintype "passive"))
      (node (ref "D4") (pin "1") (pinfunction "K_1") (pintype "passive"))
      (node (ref "H1") (pin "4") (pinfunction "4_4") (pintype "passive"))
      (node (ref "IC1") (pin "2") (pinfunction "GND_2") (pintype "passive"))
      (node (ref "IC2") (pin "1") (pinfunction "GND_1") (pintype "passive"))
      (node (ref "IC2") (pin "9") (pinfunction "EP_9") (pintype "passive"))
      (node (ref "IC3") (pin "25") (pinfunction "EP_25") (pintype "passive"))
      (node (ref "IC3") (pin "6") (pinfunction "GND_6") (pintype "passive"))
      (node (ref "J3") (pin "2") (pinfunction "2_2") (pintype "passive"))
      (node (ref "J4") (pin "2") (pinfunction "2_2") (pintype "passive"))
      (node (ref "LED1") (pin "1") (pinfunction "K_1") (pintype "passive"))
      (node (ref "LED2") (pin "1") (pinfunction "K_1") (pintype "passive"))
      (node (ref "Q1") (pin "2") (pinfunction "E_2") (pintype "passive"))
      (node (ref "Q7") (pin "1") (pinfunction "S_1") (pintype "passive"))
      (node (ref "Q7") (pin "2") (pinfunction "S_2") (pintype "passive"))
      (node (ref "Q7") (pin "3") (pinfunction "S_3") (pintype "passive"))
      (node (ref "R13") (pin "1") (pinfunction "1_1") (pintype "passive"))
      (node (ref "R18") (pin "1") (pinfunction "1_1") (pintype "passive"))
      (node (ref "R19") (pin "2") (pinfunction "2_2") (pintype "passive"))
      (node (ref "R20") (pin "2") (pinfunction "2_2") (pintype "passive"))
      (node (ref "R38") (pin "1") (pinfunction "1_1") (pintype "passive"))
      (node (ref "R39") (pin "1") (pinfunction "1_1") (pintype "passive"))
      (node (ref "R4") (pin "1") (pinfunction "1_1") (pintype "passive"))
      (node (ref "R45") (pin "1") (pinfunction "1_1") (pintype "passive"))
      (node (ref "R5") (pin "2") (pinfunction "2_2") (pintype "passive"))
      (node (ref "SW1") (pin "2") (pinfunction "2_2") (pintype "passive"))
      (node (ref "TP2") (pin "1") (pinfunction "1_1") (pintype "passive"))
      (node (ref "TP5") (pin "1") (pinfunction "1_1") (pintype "passive"))
      (node (ref "U1") (pin "19") (pinfunction "VSSA_19") (pintype "passive"))
      (node (ref "U1") (pin "23") (pinfunction "VSS_23") (pintype "passive"))
      (node (ref "U1") (pin "35") (pinfunction "VSS_35") (pintype "passive"))
      (node (ref "U1") (pin "47") (pinfunction "VSS_47") (pintype "passive"))
      (node (ref "USB1") (pin "0") (pinfunction "SHELL_0") (pintype "passive"))
      (node (ref "USB1") (pin "A1") (pinfunction "GND_A1") (pintype "passive"))
      (node (ref "USB1") (pin "A12") (pinfunction "GND_A12") (pintype "passive"))
      (node (ref "USB1") (pin "B1") (pinfunction "GND_B1") (pintype "passive"))
      (node (ref "USB1") (pin "B12") (pinfunction "GND_B12") (pintype "passive"))
      (node (ref "X1") (pin "2") (pinfunction "GND_2") (pintype "passive"))
      (node (ref "X1") (pin "4") (pinfunction "GND_4") (pintype "passive"))
    )
    (net (code "40") (name "Net-(C47-Pad2)") (class "Default")
      (node (ref "C47") (pin "2") (pinfunction "2_2") (pintype "passive"))
      (node (ref "R24") (pin "1") (pinfunction "1_1") (pintype "passive"))
    )
    (net (code "41") (name "Net-(C48-Pad2)") (class "Default")
      (node (ref "C48") (pin "2") (pinfunction "2_2") (pintype "passive"))
      (node (ref "R25") (pin "1") (pinfunction "1_1") (pintype "passive"))
    )
    (net (code "42") (name "Net-(C49-Pad2)") (class "Default")
      (node (ref "C49") (pin "2") (pinfunction "2_2") (pintype "passive"))
      (node (ref "R26") (pin "1") (pinfunction "1_1") (pintype "passive"))
    )
    (net (code "43") (name "Net-(C50-Pad1)") (class "Default")
      (node (ref "C50") (pin "1") (pinfunction "1_1") (pintype "passive"))
      (node (ref "C53") (pin "2") (pinfunction "2_2") (pintype "passive"))
      (node (ref "J1") (pin "2") (pinfunction "2_2") (pintype "passive"))
      (node (ref "Q5") (pin "1") (pinfunction "S_1") (pintype "passive"))
      (node (ref "Q5") (pin "2") (pinfunction "S_2") (pintype "passive"))
      (node (ref "Q5") (pin "3") (pinfunction "S_3") (pintype "passive"))
      (node (ref "R38") (pin "2") (pinfunction "2_2") (pintype "passive"))
    )
    (net (code "44") (name "Net-(C50-Pad2)") (class "Default")
      (node (ref "C50") (pin "2") (pinfunction "2_2") (pintype "passive"))
      (node (ref "R30") (pin "1") (pinfunction "1_1") (pintype "passive"))
    )
    (net (code "45") (name "Net-(C51-Pad1)") (class "Default")
      (node (ref "C51") (pin "1") (pinfunction "1_1") (pintype "passive"))
      (node (ref "C54") (pin "2") (pinfunction "2_2") (pintype "passive"))
      (node (ref "J2") (pin "2") (pinfunction "2_2") (pintype "passive"))
      (node (ref "Q6") (pin "1") (pinfunction "S_1") (pintype "passive"))
      (node (ref "Q6") (pin "2") (pinfunction "S_2") (pintype "passive"))
      (node (ref "Q6") (pin "3") (pinfunction "S_3") (pintype "passive"))
      (node (ref "R39") (pin "2") (pinfunction "2_2") (pintype "passive"))
    )
    (net (code "46") (name "Net-(C51-Pad2)") (class "Default")
      (node (ref "C51") (pin "2") (pinfunction "2_2") (pintype "passive"))
      (node (ref "R31") (pin "1") (pinfunction "1_1") (pintype "passive"))
    )
    (net (code "47") (name "Net-(C52-Pad2)") (class "Default")
      (node (ref "C52") (pin "2") (pinfunction "2_2") (pintype "passive"))
      (node (ref "R32") (pin "1") (pinfunction "1_1") (pintype "passive"))
    )
    (net (code "48") (name "Net-(CA-Pad1)") (class "Default")
      (node (ref "CA") (pin "1") (pinfunction "1_1") (pintype "passive"))
      (node (ref "CB") (pin "2") (pinfunction "2_2") (pintype "passive"))
      (node (ref "RA") (pin "1") (pinfunction "1_1") (pintype "passive"))
    )
    (net (code "49") (name "Net-(IC1-EN)") (class "Default")
      (node (ref "IC1") (pin "3") (pinfunction "EN_3") (pintype "passive"))
      (node (ref "R2") (pin "2") (pinfunction "2_2") (pintype "passive"))
    )
    (net (code "50") (name "Net-(IC2-BST)") (class "Default")
      (node (ref "C3") (pin "2") (pinfunction "2_2") (pintype "passive"))
      (node (ref "IC2") (pin "7") (pinfunction "BST_7") (pintype "passive"))
    )
    (net (code "51") (name "Net-(IC2-EN{slash}UVLO)") (class "Default")
      (node (ref "IC2") (pin "3") (pinfunction "EN/UVLO_3") (pintype "passive"))
      (node (ref "R3") (pin "2") (pinfunction "2_2") (pintype "passive"))
    )
    (net (code "52") (name "Net-(IC2-FB)") (class "Default")
      (node (ref "CB") (pin "1") (pinfunction "1_1") (pintype "passive"))
      (node (ref "IC2") (pin "5") (pinfunction "FB_5") (pintype "passive"))
      (node (ref "R1") (pin "1") (pinfunction "1_1") (pintype "passive"))
      (node (ref "R5") (pin "1") (pinfunction "1_1") (pintype "passive"))
    )
    (net (code "53") (name "Net-(IC2-RON)") (class "Default")
      (node (ref "IC2") (pin "4") (pinfunction "RON_4") (pintype "passive"))
      (node (ref "R4") (pin "2") (pinfunction "2_2") (pintype "passive"))
    )
    (net (code "54") (name "Net-(IC2-SW)") (class "Default")
      (node (ref "C3") (pin "1") (pinfunction "1_1") (pintype "passive"))
      (node (ref "IC2") (pin "8") (pinfunction "SW_8") (pintype "passive"))
      (node (ref "L1") (pin "1") (pinfunction "1_1") (pintype "passive"))
      (node (ref "RA") (pin "2") (pinfunction "2_2") (pintype "passive"))
    )
    (net (code "55") (name "Net-(IC4-INA+)") (class "Default")
      (node (ref "IC4") (pin "3") (pinfunction "INA+_3") (pintype "passive"))
      (node (ref "R14") (pin "1") (pinfunction "1_1") (pintype "passive"))
      (node (ref "R16") (pin "2") (pinfunction "2_2") (pintype "passive"))
    )
    (net (code "56") (name "Net-(IC4-INA-)") (class "Default")
      (node (ref "IC4") (pin "2") (pinfunction "INA-_2") (pintype "passive"))
      (node (ref "R10") (pin "2") (pinfunction "2_2") (pintype "passive"))
      (node (ref "R8") (pin "1") (pinfunction "1_1") (pintype "passive"))
    )
    (net (code "57") (name "Net-(IC4-INB+)") (class "Default")
      (node (ref "IC4") (pin "5") (pinfunction "INB+_5") (pintype "passive"))
      (node (ref "R15") (pin "2") (pinfunction "2_2") (pintype "passive"))
      (node (ref "R17") (pin "1") (pinfunction "1_1") (pintype "passive"))
    )
    (net (code "58") (name "Net-(IC4-INB-)") (class "Default")
      (node (ref "IC4") (pin "6") (pinfunction "INB-_6") (pintype "passive"))
      (node (ref "R11") (pin "1") (pinfunction "1_1") (pintype "passive"))
      (node (ref "R9") (pin "2") (pinfunction "2_2") (pintype "passive"))
    )
    (net (code "59") (name "Net-(LED1-A)") (class "Default")
      (node (ref "LED1") (pin "2") (pinfunction "A_2") (pintype "passive"))
      (node (ref "R42") (pin "2") (pinfunction "2_2") (pintype "passive"))
    )
    (net (code "60") (name "Net-(LED2-A)") (class "Default")
      (node (ref "LED2") (pin "2") (pinfunction "A_2") (pintype "passive"))
      (node (ref "R43") (pin "2") (pinfunction "2_2") (pintype "passive"))
    )
    (net (code "61") (name "Net-(Q2-G)") (class "Default")
      (node (ref "Q2") (pin "4") (pinfunction "G_4") (pintype "passive"))
      (node (ref "R27") (pin "2") (pinfunction "2_2") (pintype "passive"))
    )
    (net (code "62") (name "Net-(Q3-G)") (class "Default")
      (node (ref "Q3") (pin "4") (pinfunction "G_4") (pintype "passive"))
      (node (ref "R28") (pin "2") (pinfunction "2_2") (pintype "passive"))
    )
    (net (code "63") (name "Net-(Q4-G)") (class "Default")
      (node (ref "Q4") (pin "4") (pinfunction "G_4") (pintype "passive"))
      (node (ref "R29") (pin "2") (pinfunction "2_2") (pintype "passive"))
    )
    (net (code "64") (name "Net-(Q5-G)") (class "Default")
      (node (ref "Q5") (pin "4") (pinfunction "G_4") (pintype "passive"))
      (node (ref "R33") (pin "2") (pinfunction "2_2") (pintype "passive"))
    )
    (net (code "65") (name "Net-(Q6-G)") (class "Default")
      (node (ref "Q6") (pin "4") (pinfunction "G_4") (pintype "passive"))
      (node (ref "R34") (pin "2") (pinfunction "2_2") (pintype "passive"))
    )
    (net (code "66") (name "Net-(Q7-G)") (class "Default")
      (node (ref "Q7") (pin "4") (pinfunction "G_4") (pintype "passive"))
      (node (ref "R35") (pin "2") (pinfunction "2_2") (pintype "passive"))
    )
    (net (code "67") (name "Net-(U1-PA4)") (class "Default")
      (node (ref "R22") (pin "2") (pinfunction "2_2") (pintype "passive"))
      (node (ref "U1") (pin "12") (pinfunction "PA4_12") (pintype "passive"))
    )
    (net (code "68") (name "Net-(U1-PA6)") (class "Default")
      (node (ref "R23") (pin "2") (pinfunction "2_2") (pintype "passive"))
      (node (ref "U1") (pin "14") (pinfunction "PA6_14") (pintype "passive"))
    )
    (net (code "69") (name "Net-(U1-PB8-BOOT0)") (class "Default")
      (node (ref "R19") (pin "1") (pinfunction "1_1") (pintype "passive"))
      (node (ref "U1") (pin "45") (pinfunction "PB8-BOOT0_45") (pintype "passive"))
    )
    (net (code "70") (name "Net-(USB1-CC1)") (class "Default")
      (node (ref "R18") (pin "2") (pinfunction "2_2") (pintype "passive"))
      (node (ref "USB1") (pin "A5") (pinfunction "CC1_A5") (pintype "passive"))
    )
    (net (code "71") (name "Net-(USB1-CC2)") (class "Default")
      (node (ref "R20") (pin "1") (pinfunction "1_1") (pintype "passive"))
      (node (ref "USB1") (pin "B5") (pinfunction "CC2_B5") (pintype "passive"))
    )
    (net (code "72") (name "VBUS") (class "Default")
      (node (ref "R43") (pin "1") (pinfunction "1_1") (pintype "passive"))
      (node (ref "USB1") (pin "A4") (pinfunction "VBUS_A4") (pintype "passive"))
      (node (ref "USB1") (pin "A9") (pinfunction "VBUS_A9") (pintype "passive"))
      (node (ref "USB1") (pin "B4") (pinfunction "VBUS_B4") (pintype "passive"))
      (node (ref "USB1") (pin "B9") (pinfunction "VBUS_B9") (pintype "passive"))
    )
    (net (code "73") (name "VM") (class "Default")
      (node (ref "C10") (pin "2") (pinfunction "2_2") (pintype "passive"))
      (node (ref "C11") (pin "2") (pinfunction "2_2") (pintype "passive"))
      (node (ref "C12") (pin "2") (pinfunction "2_2") (pintype "passive"))
      (node (ref "C13") (pin "2") (pinfunction "2_2") (pintype "passive"))
      (node (ref "C14") (pin "2") (pinfunction "2_2") (pintype "passive"))
      (node (ref "C15") (pin "2") (pinfunction "2_2") (pintype "passive"))
      (node (ref "C16") (pin "2") (pinfunction "2_2") (pintype "passive"))
      (node (ref "C20") (pin "2") (pinfunction "2_2") (pintype "passive"))
      (node (ref "C21") (pin "2") (pinfunction "2_2") (pintype "passive"))
      (node (ref "C4") (pin "2") (pinfunction "2_2") (pintype "passive"))
      (node (ref "C5") (pin "2") (pinfunction "2_2") (pintype "passive"))
      (node (ref "C6") (pin "2") (pinfunction "2_2") (pintype "passive"))
      (node (ref "C7") (pin "2") (pinfunction "2_2") (pintype "passive"))
      (node (ref "C8") (pin "2") (pinfunction "2_2") (pintype "passive"))
      (node (ref "C9") (pin "2") (pinfunction "2_2") (pintype "passive"))
      (node (ref "D1") (pin "2") (pinfunction "2_2") (pintype "passive"))
      (node (ref "L2") (pin "1") (pinfunction "1_1") (pintype "passive"))
      (node (ref "Q2") (pin "5") (pinfunction "D_5") (pintype "passive"))
      (node (ref "Q2") (pin "6") (pinfunction "D_6") (pintype "passive"))
      (node (ref "Q2") (pin "7") (pinfunction "D_7") (pintype "passive"))
      (node (ref "Q2") (pin "8") (pinfunction "D_8") (pintype "passive"))
      (node (ref "Q2") (pin "9") (pinfunction "D_9") (pintype "passive"))
      (node (ref "Q3") (pin "5") (pinfunction "D_5") (pintype "passive"))
      (node (ref "Q3") (pin "6") (pinfunction "D_6") (pintype "passive"))
      (node (ref "Q3") (pin "7") (pinfunction "D_7") (pintype "passive"))
      (node (ref "Q3") (pin "8") (pinfunction "D_8") (pintype "passive"))
      (node (ref "Q3") (pin "9") (pinfunction "D_9") (pintype "passive"))
      (node (ref "Q4") (pin "5") (pinfunction "D_5") (pintype "passive"))
      (node (ref "Q4") (pin "6") (pinfunction "D_6") (pintype "passive"))
      (node (ref "Q4") (pin "7") (pinfunction "D_7") (pintype "passive"))
      (node (ref "Q4") (pin "8") (pinfunction "D_8") (pintype "passive"))
      (node (ref "Q4") (pin "9") (pinfunction "D_9") (pintype "passive"))
      (node (ref "R24") (pin "2") (pinfunction "2_2") (pintype "passive"))
      (node (ref "R25") (pin "2") (pinfunction "2_2") (pintype "passive"))
      (node (ref "R26") (pin "2") (pinfunction "2_2") (pintype "passive"))
      (node (ref "TP1") (pin "1") (pinfunction "1_1") (pintype "passive"))
    )
    (net (code "74") (name "VSYS") (class "Default")
      (node (ref "C2") (pin "2") (pinfunction "2_2") (pintype "passive"))
      (node (ref "C22") (pin "2") (pinfunction "2_2") (pintype "passive"))
      (node (ref "C26") (pin "2") (pinfunction "2_2") (pintype "passive"))
      (node (ref "IC2") (pin "2") (pinfunction "VIN_2") (pintype "passive"))
      (node (ref "L2") (pin "2") (pinfunction "2_2") (pintype "passive"))
      (node (ref "R3") (pin "1") (pinfunction "1_1") (pintype "passive"))
    )
    (net (code "75") (name "unconnected-(IC1-NC-Pad4)") (class "Default")
      (node (ref "IC1") (pin "4") (pinfunction "NC_4") (pintype "passive+no_connect"))
    )
    (net (code "76") (name "unconnected-(IC2-PGOOD-Pad6)") (class "Default")
      (node (ref "IC2") (pin "6") (pinfunction "PGOOD_6") (pintype "passive+no_connect"))
    )
    (net (code "77") (name "unconnected-(IC3-DT-Pad21)") (class "Default")
      (node (ref "IC3") (pin "21") (pinfunction "DT_21") (pintype "passive+no_connect"))
    )
    (net (code "78") (name "unconnected-(IC3-MODE-Pad5)") (class "Default")
      (node (ref "IC3") (pin "5") (pinfunction "MODE_5") (pintype "passive+no_connect"))
    )
    (net (code "79") (name "unconnected-(IC3-NC-Pad7)") (class "Default")
      (node (ref "IC3") (pin "7") (pinfunction "NC_7") (pintype "passive+no_connect"))
    )
    (net (code "80") (name "unconnected-(IC3-NC-Pad8)") (class "Default")
      (node (ref "IC3") (pin "8") (pinfunction "NC_8") (pintype "passive+no_connect"))
    )
    (net (code "81") (name "unconnected-(U1-PA0-Pad8)") (class "Default")
      (node (ref "U1") (pin "8") (pinfunction "PA0_8") (pintype "passive+no_connect"))
    )
    (net (code "82") (name "unconnected-(U1-PA3-Pad11)") (class "Default")
      (node (ref "U1") (pin "11") (pinfunction "PA3_11") (pintype "passive+no_connect"))
    )
    (net (code "83") (name "unconnected-(U1-PA5-Pad13)") (class "Default")
      (node (ref "U1") (pin "13") (pinfunction "PA5_13") (pintype "passive"))
    )
    (net (code "84") (name "unconnected-(U1-PA7-Pad15)") (class "Default")
      (node (ref "U1") (pin "15") (pinfunction "PA7_15") (pintype "passive+no_connect"))
    )
    (net (code "85") (name "unconnected-(U1-PA11-Pad33)") (class "Default")
      (node (ref "U1") (pin "33") (pinfunction "PA11_33") (pintype "passive"))
    )
    (net (code "86") (name "unconnected-(U1-PA12-Pad34)") (class "Default")
      (node (ref "U1") (pin "34") (pinfunction "PA12_34") (pintype "passive"))
    )
    (net (code "87") (name "unconnected-(U1-PA15-Pad39)") (class "Default")
      (node (ref "U1") (pin "39") (pinfunction "PA15_39") (pintype "passive+no_connect"))
    )
    (net (code "88") (name "unconnected-(U1-PB0-Pad16)") (class "Default")
      (node (ref "U1") (pin "16") (pinfunction "PB0_16") (pintype "passive+no_connect"))
    )
    (net (code "89") (name "unconnected-(U1-PB1-Pad17)") (class "Default")
      (node (ref "U1") (pin "17") (pinfunction "PB1_17") (pintype "passive+no_connect"))
    )
    (net (code "90") (name "unconnected-(U1-PB2-Pad18)") (class "Default")
      (node (ref "U1") (pin "18") (pinfunction "PB2_18") (pintype "passive+no_connect"))
    )
    (net (code "91") (name "unconnected-(U1-PB3-Pad40)") (class "Default")
      (node (ref "U1") (pin "40") (pinfunction "PB3_40") (pintype "passive+no_connect"))
    )
    (net (code "92") (name "unconnected-(U1-PB4-Pad41)") (class "Default")
      (node (ref "U1") (pin "41") (pinfunction "PB4_41") (pintype "passive+no_connect"))
    )
    (net (code "93") (name "unconnected-(U1-PB5-Pad42)") (class "Default")
      (node (ref "U1") (pin "42") (pinfunction "PB5_42") (pintype "passive+no_connect"))
    )
    (net (code "94") (name "unconnected-(U1-PB7-Pad44)") (class "Default")
      (node (ref "U1") (pin "44") (pinfunction "PB7_44") (pintype "passive+no_connect"))
    )
    (net (code "95") (name "unconnected-(U1-PB9-Pad46)") (class "Default")
      (node (ref "U1") (pin "46") (pinfunction "PB9_46") (pintype "passive+no_connect"))
    )
    (net (code "96") (name "unconnected-(U1-PB10-Pad22)") (class "Default")
      (node (ref "U1") (pin "22") (pinfunction "PB10_22") (pintype "passive+no_connect"))
    )
    (net (code "97") (name "unconnected-(U1-PC13-Pad2)") (class "Default")
      (node (ref "U1") (pin "2") (pinfunction "PC13_2") (pintype "passive+no_connect"))
    )
    (net (code "98") (name "unconnected-(U1-PC14-OSC32_IN-Pad3)") (class "Default")
      (node (ref "U1") (pin "3") (pinfunction "PC14-OSC32_IN_3") (pintype "passive+no_connect"))
    )
    (net (code "99") (name "unconnected-(U1-PC15-OSC32_OUT-Pad4)") (class "Default")
      (node (ref "U1") (pin "4") (pinfunction "PC15-OSC32_OUT_4") (pintype "passive+no_connect"))
    )
    (net (code "100") (name "unconnected-(USB1-SBU1-PadA8)") (class "Default")
      (node (ref "USB1") (pin "A8") (pinfunction "SBU1_A8") (pintype "passive+no_connect"))
    )
    (net (code "101") (name "unconnected-(USB1-SBU2-PadB8)") (class "Default")
      (node (ref "USB1") (pin "B8") (pinfunction "SBU2_B8") (pintype "passive+no_connect"))
    )
    (net (code "102") (name "unconnected-(USB1-SSRXN1-PadB10)") (class "Default")
      (node (ref "USB1") (pin "B10") (pinfunction "SSRXN1_B10") (pintype "passive+no_connect"))
    )
    (net (code "103") (name "unconnected-(USB1-SSRXN2-PadA10)") (class "Default")
      (node (ref "USB1") (pin "A10") (pinfunction "SSRXN2_A10") (pintype "passive+no_connect"))
    )
    (net (code "104") (name "unconnected-(USB1-SSRXP1-PadB11)") (class "Default")
      (node (ref "USB1") (pin "B11") (pinfunction "SSRXP1_B11") (pintype "passive+no_connect"))
    )
    (net (code "105") (name "unconnected-(USB1-SSRXP2-PadA11)") (class "Default")
      (node (ref "USB1") (pin "A11") (pinfunction "SSRXP2_A11") (pintype "passive+no_connect"))
    )
    (net (code "106") (name "unconnected-(USB1-SSTXN1-PadA3)") (class "Default")
      (node (ref "USB1") (pin "A3") (pinfunction "SSTXN1_A3") (pintype "passive+no_connect"))
    )
    (net (code "107") (name "unconnected-(USB1-SSTXN2-PadB3)") (class "Default")
      (node (ref "USB1") (pin "B3") (pinfunction "SSTXN2_B3") (pintype "passive+no_connect"))
    )
    (net (code "108") (name "unconnected-(USB1-SSTXP1-PadA2)") (class "Default")
      (node (ref "USB1") (pin "A2") (pinfunction "SSTXP1_A2") (pintype "passive+no_connect"))
    )
    (net (code "109") (name "unconnected-(USB1-SSTXP2-PadB2)") (class "Default")
      (node (ref "USB1") (pin "B2") (pinfunction "SSTXP2_B2") (pintype "passive+no_connect"))
    )
  )
)
